# Potentiometer_and_LEDs.net
KiCad netlist of a schematic drawn in Altium Designer
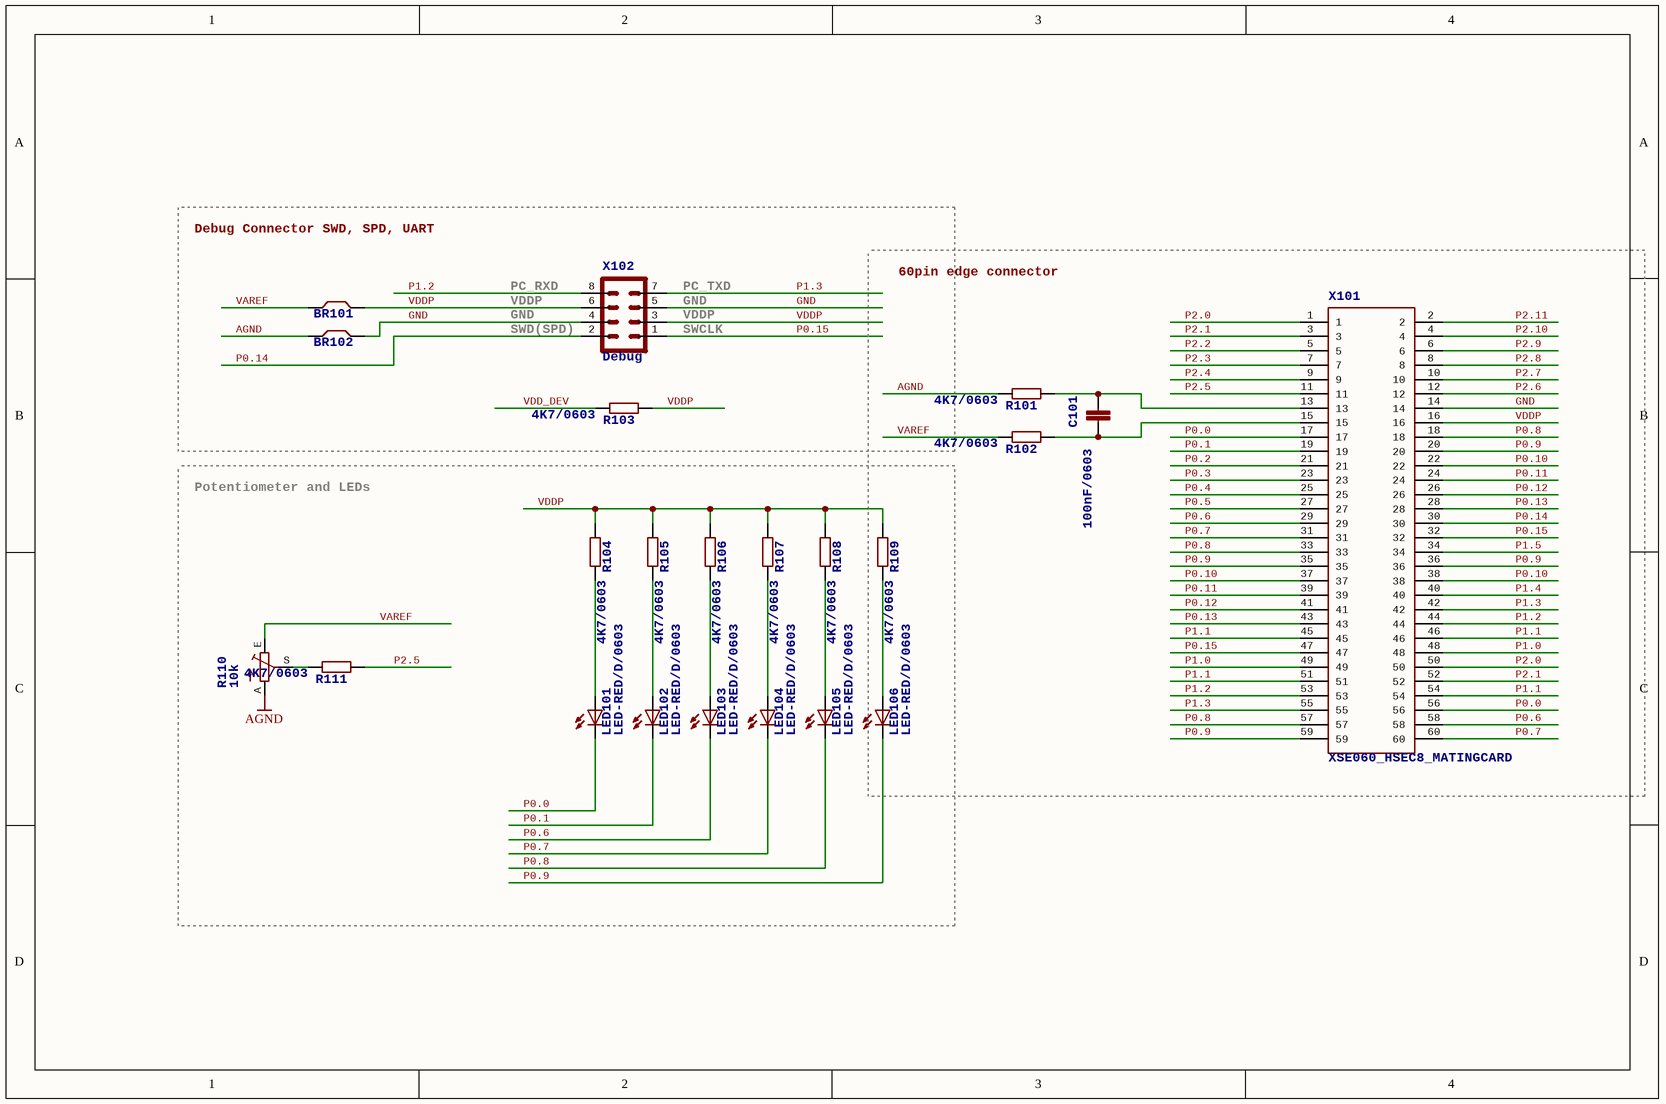
[diagram p0: Potentiometer and LEDs.SchDoc]

(export (version "E")
  (design (tool "Eeschema 10.0.6"))
  (components
    (comp (ref "BR101")
      (value "BRIDGE12X12")
      (footprint "BRIDGE12")
      (libsource (lib "sucaiku") (part "BRIDGE12X12"))
    )
    (comp (ref "BR102")
      (value "BRIDGE12X12")
      (footprint "BRIDGE12")
      (libsource (lib "sucaiku") (part "BRIDGE12X12"))
    )
    (comp (ref "C101")
      (value "100nF/0603")
      (footprint "RCL_C0603")
      (description "CAPACITOR, European symbol")
      (libsource (lib "sucaiku") (part "RCL_C-EUC0603"))
    )
    (comp (ref "LED101")
      (value "LED-RED/D/0603")
      (footprint "LED_CHIP-LED0603")
      (libsource (lib "sucaiku") (part "LED_LEDCHIP-LED0603"))
    )
    (comp (ref "LED102")
      (value "LED-RED/D/0603")
      (footprint "LED_CHIP-LED0603")
      (libsource (lib "sucaiku") (part "LED_LEDCHIP-LED0603"))
    )
    (comp (ref "LED103")
      (value "LED-RED/D/0603")
      (footprint "LED_CHIP-LED0603")
      (libsource (lib "sucaiku") (part "LED_LEDCHIP-LED0603"))
    )
    (comp (ref "LED104")
      (value "LED-RED/D/0603")
      (footprint "LED_CHIP-LED0603")
      (libsource (lib "sucaiku") (part "LED_LEDCHIP-LED0603"))
    )
    (comp (ref "LED105")
      (value "LED-RED/D/0603")
      (footprint "LED_CHIP-LED0603")
      (libsource (lib "sucaiku") (part "LED_LEDCHIP-LED0603"))
    )
    (comp (ref "LED106")
      (value "LED-RED/D/0603")
      (footprint "LED_CHIP-LED0603")
      (libsource (lib "sucaiku") (part "LED_LEDCHIP-LED0603"))
    )
    (comp (ref "R101")
      (value "4K7/0603")
      (footprint "DSR_R0603")
      (libsource (lib "sucaiku") (part "DSR_R-EU_R0603"))
    )
    (comp (ref "R102")
      (value "4K7/0603")
      (footprint "DSR_R0603")
      (libsource (lib "sucaiku") (part "DSR_R-EU_R0603"))
    )
    (comp (ref "R103")
      (value "4K7/0603")
      (footprint "DSR_R0603")
      (libsource (lib "sucaiku") (part "DSR_R-EU_R0603"))
    )
    (comp (ref "R104")
      (value "4K7/0603")
      (footprint "DSR_R0603")
      (libsource (lib "sucaiku") (part "DSR_R-EU_R0603"))
    )
    (comp (ref "R105")
      (value "4K7/0603")
      (footprint "DSR_R0603")
      (libsource (lib "sucaiku") (part "DSR_R-EU_R0603"))
    )
    (comp (ref "R106")
      (value "4K7/0603")
      (footprint "DSR_R0603")
      (libsource (lib "sucaiku") (part "DSR_R-EU_R0603"))
    )
    (comp (ref "R107")
      (value "4K7/0603")
      (footprint "DSR_R0603")
      (libsource (lib "sucaiku") (part "DSR_R-EU_R0603"))
    )
    (comp (ref "R108")
      (value "4K7/0603")
      (footprint "DSR_R0603")
      (libsource (lib "sucaiku") (part "DSR_R-EU_R0603"))
    )
    (comp (ref "R109")
      (value "4K7/0603")
      (footprint "DSR_R0603")
      (libsource (lib "sucaiku") (part "DSR_R-EU_R0603"))
    )
    (comp (ref "R110")
      (value "10k")
      (footprint "B25P")
      (description "POTENTIOMETER")
      (libsource (lib "sucaiku") (part "TRIM_EU-B25P"))
    )
    (comp (ref "R111")
      (value "4K7/0603")
      (footprint "DSR_R0603")
      (libsource (lib "sucaiku") (part "DSR_R-EU_R0603"))
    )
    (comp (ref "X101")
      (value "XSE060_HSEC8_MATINGCARD")
      (footprint "XSE060_HSEC8_MATINGCARD_60")
      (libsource (lib "sucaiku") (part "XSE060_HSEC8_MATINGCARD"))
    )
    (comp (ref "X102")
      (value "Debug")
      (footprint "MA04-2")
      (description "PIN HEADER")
      (libsource (lib "sucaiku") (part "MA04-2"))
    )
  )
  (nets
    (net (code "1") (name "/GND") (class "Default")
      (node (ref "BR102") (pin "B2") (pinfunction "B2_B2") (pintype "passive"))
      (node (ref "X101") (pin "14") (pinfunction "14_14") (pintype "passive"))
      (node (ref "X102") (pin "4") (pinfunction "4_4") (pintype "passive"))
      (node (ref "X102") (pin "5") (pinfunction "5_5") (pintype "passive"))
    )
    (net (code "2") (name "/P0.0") (class "Default")
      (node (ref "LED101") (pin "C") (pinfunction "C_C") (pintype "passive"))
      (node (ref "X101") (pin "17") (pinfunction "17_17") (pintype "passive"))
      (node (ref "X101") (pin "56") (pinfunction "56_56") (pintype "passive"))
    )
    (net (code "3") (name "/P0.1") (class "Default")
      (node (ref "LED102") (pin "C") (pinfunction "C_C") (pintype "passive"))
      (node (ref "X101") (pin "19") (pinfunction "19_19") (pintype "passive"))
    )
    (net (code "4") (name "/P0.2") (class "Default")
      (node (ref "X101") (pin "21") (pinfunction "21_21") (pintype "passive"))
    )
    (net (code "5") (name "/P0.3") (class "Default")
      (node (ref "X101") (pin "23") (pinfunction "23_23") (pintype "passive"))
    )
    (net (code "6") (name "/P0.4") (class "Default")
      (node (ref "X101") (pin "25") (pinfunction "25_25") (pintype "passive"))
    )
    (net (code "7") (name "/P0.5") (class "Default")
      (node (ref "X101") (pin "27") (pinfunction "27_27") (pintype "passive"))
    )
    (net (code "8") (name "/P0.6") (class "Default")
      (node (ref "LED103") (pin "C") (pinfunction "C_C") (pintype "passive"))
      (node (ref "X101") (pin "29") (pinfunction "29_29") (pintype "passive"))
      (node (ref "X101") (pin "58") (pinfunction "58_58") (pintype "passive"))
    )
    (net (code "9") (name "/P0.7") (class "Default")
      (node (ref "LED104") (pin "C") (pinfunction "C_C") (pintype "passive"))
      (node (ref "X101") (pin "31") (pinfunction "31_31") (pintype "passive"))
      (node (ref "X101") (pin "60") (pinfunction "60_60") (pintype "passive"))
    )
    (net (code "10") (name "/P0.8") (class "Default")
      (node (ref "LED105") (pin "C") (pinfunction "C_C") (pintype "passive"))
      (node (ref "X101") (pin "18") (pinfunction "18_18") (pintype "passive"))
      (node (ref "X101") (pin "33") (pinfunction "33_33") (pintype "passive"))
      (node (ref "X101") (pin "57") (pinfunction "57_57") (pintype "passive"))
    )
    (net (code "11") (name "/P0.9") (class "Default")
      (node (ref "LED106") (pin "C") (pinfunction "C_C") (pintype "passive"))
      (node (ref "X101") (pin "20") (pinfunction "20_20") (pintype "passive"))
      (node (ref "X101") (pin "35") (pinfunction "35_35") (pintype "passive"))
      (node (ref "X101") (pin "36") (pinfunction "36_36") (pintype "passive"))
      (node (ref "X101") (pin "59") (pinfunction "59_59") (pintype "passive"))
    )
    (net (code "12") (name "/P0.10") (class "Default")
      (node (ref "X101") (pin "22") (pinfunction "22_22") (pintype "passive"))
      (node (ref "X101") (pin "37") (pinfunction "37_37") (pintype "passive"))
      (node (ref "X101") (pin "38") (pinfunction "38_38") (pintype "passive"))
    )
    (net (code "13") (name "/P0.11") (class "Default")
      (node (ref "X101") (pin "24") (pinfunction "24_24") (pintype "passive"))
      (node (ref "X101") (pin "39") (pinfunction "39_39") (pintype "passive"))
    )
    (net (code "14") (name "/P0.12") (class "Default")
      (node (ref "X101") (pin "26") (pinfunction "26_26") (pintype "passive"))
      (node (ref "X101") (pin "41") (pinfunction "41_41") (pintype "passive"))
    )
    (net (code "15") (name "/P0.13") (class "Default")
      (node (ref "X101") (pin "28") (pinfunction "28_28") (pintype "passive"))
      (node (ref "X101") (pin "43") (pinfunction "43_43") (pintype "passive"))
    )
    (net (code "16") (name "/P0.14") (class "Default")
      (node (ref "X101") (pin "30") (pinfunction "30_30") (pintype "passive"))
      (node (ref "X102") (pin "2") (pinfunction "2_2") (pintype "passive"))
    )
    (net (code "17") (name "/P0.15") (class "Default")
      (node (ref "X101") (pin "32") (pinfunction "32_32") (pintype "passive"))
      (node (ref "X101") (pin "47") (pinfunction "47_47") (pintype "passive"))
      (node (ref "X102") (pin "1") (pinfunction "1_1") (pintype "passive"))
    )
    (net (code "18") (name "/P1.0") (class "Default")
      (node (ref "X101") (pin "48") (pinfunction "48_48") (pintype "passive"))
      (node (ref "X101") (pin "49") (pinfunction "49_49") (pintype "passive"))
    )
    (net (code "19") (name "/P1.1") (class "Default")
      (node (ref "X101") (pin "45") (pinfunction "45_45") (pintype "passive"))
      (node (ref "X101") (pin "46") (pinfunction "46_46") (pintype "passive"))
      (node (ref "X101") (pin "51") (pinfunction "51_51") (pintype "passive"))
      (node (ref "X101") (pin "54") (pinfunction "54_54") (pintype "passive"))
    )
    (net (code "20") (name "/P1.2") (class "Default")
      (node (ref "X101") (pin "44") (pinfunction "44_44") (pintype "passive"))
      (node (ref "X101") (pin "53") (pinfunction "53_53") (pintype "passive"))
      (node (ref "X102") (pin "8") (pinfunction "8_8") (pintype "passive"))
    )
    (net (code "21") (name "/P1.3") (class "Default")
      (node (ref "X101") (pin "42") (pinfunction "42_42") (pintype "passive"))
      (node (ref "X101") (pin "55") (pinfunction "55_55") (pintype "passive"))
      (node (ref "X102") (pin "7") (pinfunction "7_7") (pintype "passive"))
    )
    (net (code "22") (name "/P1.4") (class "Default")
      (node (ref "X101") (pin "40") (pinfunction "40_40") (pintype "passive"))
    )
    (net (code "23") (name "/P1.5") (class "Default")
      (node (ref "X101") (pin "34") (pinfunction "34_34") (pintype "passive"))
    )
    (net (code "24") (name "/P2.0") (class "Default")
      (node (ref "X101") (pin "1") (pinfunction "1_1") (pintype "passive"))
      (node (ref "X101") (pin "50") (pinfunction "50_50") (pintype "passive"))
    )
    (net (code "25") (name "/P2.1") (class "Default")
      (node (ref "X101") (pin "3") (pinfunction "3_3") (pintype "passive"))
      (node (ref "X101") (pin "52") (pinfunction "52_52") (pintype "passive"))
    )
    (net (code "26") (name "/P2.2") (class "Default")
      (node (ref "X101") (pin "5") (pinfunction "5_5") (pintype "passive"))
    )
    (net (code "27") (name "/P2.3") (class "Default")
      (node (ref "X101") (pin "7") (pinfunction "7_7") (pintype "passive"))
    )
    (net (code "28") (name "/P2.4") (class "Default")
      (node (ref "X101") (pin "9") (pinfunction "9_9") (pintype "passive"))
    )
    (net (code "29") (name "/P2.5") (class "Default")
      (node (ref "R111") (pin "1") (pinfunction "1_1") (pintype "passive"))
      (node (ref "X101") (pin "11") (pinfunction "11_11") (pintype "passive"))
    )
    (net (code "30") (name "/P2.6") (class "Default")
      (node (ref "X101") (pin "12") (pinfunction "12_12") (pintype "passive"))
    )
    (net (code "31") (name "/P2.7") (class "Default")
      (node (ref "X101") (pin "10") (pinfunction "10_10") (pintype "passive"))
    )
    (net (code "32") (name "/P2.8") (class "Default")
      (node (ref "X101") (pin "8") (pinfunction "8_8") (pintype "passive"))
    )
    (net (code "33") (name "/P2.9") (class "Default")
      (node (ref "X101") (pin "6") (pinfunction "6_6") (pintype "passive"))
    )
    (net (code "34") (name "/P2.10") (class "Default")
      (node (ref "X101") (pin "4") (pinfunction "4_4") (pintype "passive"))
    )
    (net (code "35") (name "/P2.11") (class "Default")
      (node (ref "X101") (pin "2") (pinfunction "2_2") (pintype "passive"))
    )
    (net (code "36") (name "/VAREF") (class "Default")
      (node (ref "BR101") (pin "B1") (pinfunction "B1_B1") (pintype "passive"))
      (node (ref "R102") (pin "2") (pinfunction "2_2") (pintype "passive"))
      (node (ref "R110") (pin "E") (pinfunction "E_E") (pintype "passive"))
    )
    (net (code "37") (name "/VDDP") (class "Default")
      (node (ref "BR101") (pin "B2") (pinfunction "B2_B2") (pintype "passive"))
      (node (ref "R103") (pin "1") (pinfunction "1_1") (pintype "passive"))
      (node (ref "R104") (pin "1") (pinfunction "1_1") (pintype "passive"))
      (node (ref "R105") (pin "1") (pinfunction "1_1") (pintype "passive"))
      (node (ref "R106") (pin "1") (pinfunction "1_1") (pintype "passive"))
      (node (ref "R107") (pin "1") (pinfunction "1_1") (pintype "passive"))
      (node (ref "R108") (pin "1") (pinfunction "1_1") (pintype "passive"))
      (node (ref "R109") (pin "1") (pinfunction "1_1") (pintype "passive"))
      (node (ref "X101") (pin "16") (pinfunction "16_16") (pintype "passive"))
      (node (ref "X102") (pin "3") (pinfunction "3_3") (pintype "passive"))
      (node (ref "X102") (pin "6") (pinfunction "6_6") (pintype "passive"))
    )
    (net (code "38") (name "/VDD_DEV") (class "Default")
      (node (ref "R103") (pin "2") (pinfunction "2_2") (pintype "passive"))
    )
    (net (code "39") (name "AGND") (class "Default")
      (node (ref "BR102") (pin "B1") (pinfunction "B1_B1") (pintype "passive"))
      (node (ref "R101") (pin "2") (pinfunction "2_2") (pintype "passive"))
      (node (ref "R110") (pin "A") (pinfunction "A_A") (pintype "passive"))
    )
    (net (code "40") (name "Net-(C101-Pad1)") (class "Default")
      (node (ref "C101") (pin "1") (pinfunction "1_1") (pintype "passive"))
      (node (ref "R101") (pin "1") (pinfunction "1_1") (pintype "passive"))
      (node (ref "X101") (pin "13") (pinfunction "13_13") (pintype "passive"))
    )
    (net (code "41") (name "Net-(C101-Pad2)") (class "Default")
      (node (ref "C101") (pin "2") (pinfunction "2_2") (pintype "passive"))
      (node (ref "R102") (pin "1") (pinfunction "1_1") (pintype "passive"))
      (node (ref "X101") (pin "15") (pinfunction "15_15") (pintype "passive"))
    )
    (net (code "42") (name "Net-(LED101-PadA)") (class "Default")
      (node (ref "LED101") (pin "A") (pinfunction "A_A") (pintype "passive"))
      (node (ref "R104") (pin "2") (pinfunction "2_2") (pintype "passive"))
    )
    (net (code "43") (name "Net-(LED102-PadA)") (class "Default")
      (node (ref "LED102") (pin "A") (pinfunction "A_A") (pintype "passive"))
      (node (ref "R105") (pin "2") (pinfunction "2_2") (pintype "passive"))
    )
    (net (code "44") (name "Net-(LED103-PadA)") (class "Default")
      (node (ref "LED103") (pin "A") (pinfunction "A_A") (pintype "passive"))
      (node (ref "R106") (pin "2") (pinfunction "2_2") (pintype "passive"))
    )
    (net (code "45") (name "Net-(LED104-PadA)") (class "Default")
      (node (ref "LED104") (pin "A") (pinfunction "A_A") (pintype "passive"))
      (node (ref "R107") (pin "2") (pinfunction "2_2") (pintype "passive"))
    )
    (net (code "46") (name "Net-(LED105-PadA)") (class "Default")
      (node (ref "LED105") (pin "A") (pinfunction "A_A") (pintype "passive"))
      (node (ref "R108") (pin "2") (pinfunction "2_2") (pintype "passive"))
    )
    (net (code "47") (name "Net-(LED106-PadA)") (class "Default")
      (node (ref "LED106") (pin "A") (pinfunction "A_A") (pintype "passive"))
      (node (ref "R109") (pin "2") (pinfunction "2_2") (pintype "passive"))
    )
    (net (code "48") (name "Net-(R110-PadS)") (class "Default")
      (node (ref "R110") (pin "S") (pinfunction "S_S") (pintype "passive"))
      (node (ref "R111") (pin "2") (pinfunction "2_2") (pintype "passive"))
    )
  )
)
